# SSD_PINOUT.net
KiCad netlist of a schematic drawn in Altium Designer
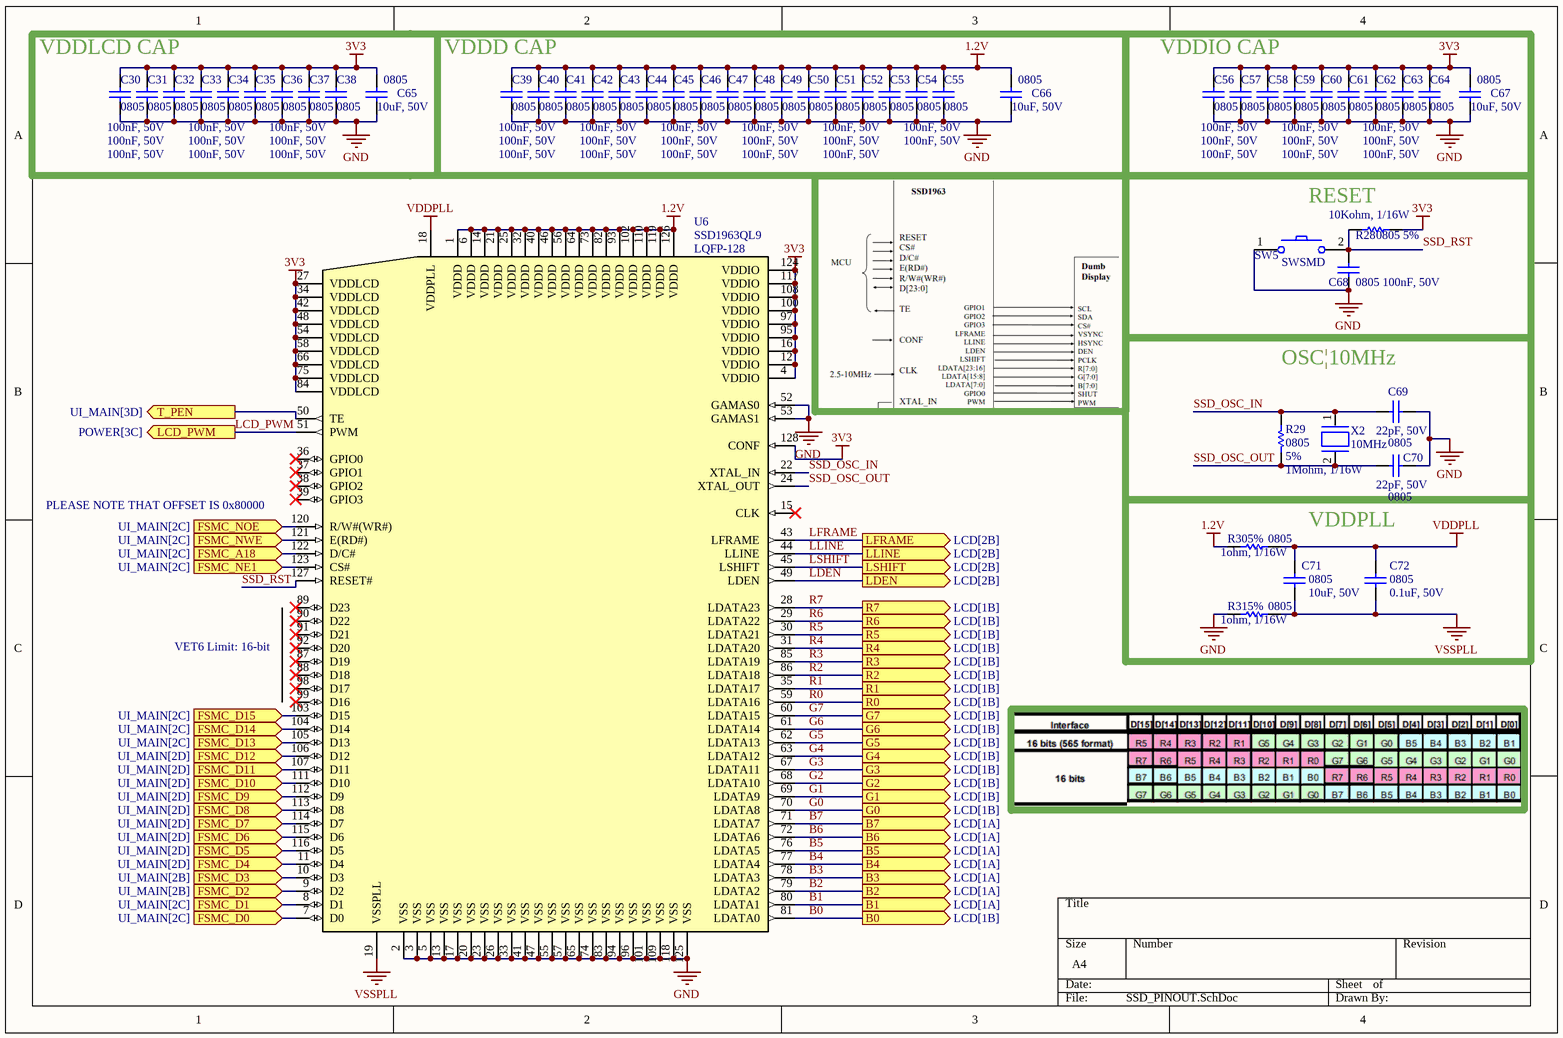
[diagram p0: SSD_PINOUT.SchDoc]

(export (version "E")
  (design (tool "Eeschema 10.0.6"))
  (components
    (comp (ref "C30")
      (value "100nF, 50V")
      (footprint "C_0805")
      (description "CAP_0805")
      (fields (field (name "PACKAGE") "0805"))
      (libsource (lib "DisplayLib") (part "CAP_0805"))
    )
    (comp (ref "C31")
      (value "100nF, 50V")
      (footprint "C_0805")
      (description "CAP_0805")
      (fields (field (name "PACKAGE") "0805"))
      (libsource (lib "DisplayLib") (part "CAP_0805"))
    )
    (comp (ref "C32")
      (value "100nF, 50V")
      (footprint "C_0805")
      (description "CAP_0805")
      (fields (field (name "PACKAGE") "0805"))
      (libsource (lib "DisplayLib") (part "CAP_0805"))
    )
    (comp (ref "C33")
      (value "100nF, 50V")
      (footprint "C_0805")
      (description "CAP_0805")
      (fields (field (name "PACKAGE") "0805"))
      (libsource (lib "DisplayLib") (part "CAP_0805"))
    )
    (comp (ref "C34")
      (value "100nF, 50V")
      (footprint "C_0805")
      (description "CAP_0805")
      (fields (field (name "PACKAGE") "0805"))
      (libsource (lib "DisplayLib") (part "CAP_0805"))
    )
    (comp (ref "C35")
      (value "100nF, 50V")
      (footprint "C_0805")
      (description "CAP_0805")
      (fields (field (name "PACKAGE") "0805"))
      (libsource (lib "DisplayLib") (part "CAP_0805"))
    )
    (comp (ref "C36")
      (value "100nF, 50V")
      (footprint "C_0805")
      (description "CAP_0805")
      (fields (field (name "PACKAGE") "0805"))
      (libsource (lib "DisplayLib") (part "CAP_0805"))
    )
    (comp (ref "C37")
      (value "100nF, 50V")
      (footprint "C_0805")
      (description "CAP_0805")
      (fields (field (name "PACKAGE") "0805"))
      (libsource (lib "DisplayLib") (part "CAP_0805"))
    )
    (comp (ref "C38")
      (value "100nF, 50V")
      (footprint "C_0805")
      (description "CAP_0805")
      (fields (field (name "PACKAGE") "0805"))
      (libsource (lib "DisplayLib") (part "CAP_0805"))
    )
    (comp (ref "C39")
      (value "100nF, 50V")
      (footprint "C_0805")
      (description "CAP_0805")
      (fields (field (name "PACKAGE") "0805"))
      (libsource (lib "DisplayLib") (part "CAP_0805"))
    )
    (comp (ref "C40")
      (value "100nF, 50V")
      (footprint "C_0805")
      (description "CAP_0805")
      (fields (field (name "PACKAGE") "0805"))
      (libsource (lib "DisplayLib") (part "CAP_0805"))
    )
    (comp (ref "C41")
      (value "100nF, 50V")
      (footprint "C_0805")
      (description "CAP_0805")
      (fields (field (name "PACKAGE") "0805"))
      (libsource (lib "DisplayLib") (part "CAP_0805"))
    )
    (comp (ref "C42")
      (value "100nF, 50V")
      (footprint "C_0805")
      (description "CAP_0805")
      (fields (field (name "PACKAGE") "0805"))
      (libsource (lib "DisplayLib") (part "CAP_0805"))
    )
    (comp (ref "C43")
      (value "100nF, 50V")
      (footprint "C_0805")
      (description "CAP_0805")
      (fields (field (name "PACKAGE") "0805"))
      (libsource (lib "DisplayLib") (part "CAP_0805"))
    )
    (comp (ref "C44")
      (value "100nF, 50V")
      (footprint "C_0805")
      (description "CAP_0805")
      (fields (field (name "PACKAGE") "0805"))
      (libsource (lib "DisplayLib") (part "CAP_0805"))
    )
    (comp (ref "C45")
      (value "100nF, 50V")
      (footprint "C_0805")
      (description "CAP_0805")
      (fields (field (name "PACKAGE") "0805"))
      (libsource (lib "DisplayLib") (part "CAP_0805"))
    )
    (comp (ref "C46")
      (value "100nF, 50V")
      (footprint "C_0805")
      (description "CAP_0805")
      (fields (field (name "PACKAGE") "0805"))
      (libsource (lib "DisplayLib") (part "CAP_0805"))
    )
    (comp (ref "C47")
      (value "100nF, 50V")
      (footprint "C_0805")
      (description "CAP_0805")
      (fields (field (name "PACKAGE") "0805"))
      (libsource (lib "DisplayLib") (part "CAP_0805"))
    )
    (comp (ref "C48")
      (value "100nF, 50V")
      (footprint "C_0805")
      (description "CAP_0805")
      (fields (field (name "PACKAGE") "0805"))
      (libsource (lib "DisplayLib") (part "CAP_0805"))
    )
    (comp (ref "C49")
      (value "100nF, 50V")
      (footprint "C_0805")
      (description "CAP_0805")
      (fields (field (name "PACKAGE") "0805"))
      (libsource (lib "DisplayLib") (part "CAP_0805"))
    )
    (comp (ref "C50")
      (value "100nF, 50V")
      (footprint "C_0805")
      (description "CAP_0805")
      (fields (field (name "PACKAGE") "0805"))
      (libsource (lib "DisplayLib") (part "CAP_0805"))
    )
    (comp (ref "C51")
      (value "100nF, 50V")
      (footprint "C_0805")
      (description "CAP_0805")
      (fields (field (name "PACKAGE") "0805"))
      (libsource (lib "DisplayLib") (part "CAP_0805"))
    )
    (comp (ref "C52")
      (value "100nF, 50V")
      (footprint "C_0805")
      (description "CAP_0805")
      (fields (field (name "PACKAGE") "0805"))
      (libsource (lib "DisplayLib") (part "CAP_0805"))
    )
    (comp (ref "C53")
      (value "100nF, 50V")
      (footprint "C_0805")
      (description "CAP_0805")
      (fields (field (name "PACKAGE") "0805"))
      (libsource (lib "DisplayLib") (part "CAP_0805"))
    )
    (comp (ref "C54")
      (value "100nF, 50V")
      (footprint "C_0805")
      (description "CAP_0805")
      (fields (field (name "PACKAGE") "0805"))
      (libsource (lib "DisplayLib") (part "CAP_0805"))
    )
    (comp (ref "C55")
      (value "100nF, 50V")
      (footprint "C_0805")
      (description "CAP_0805")
      (fields (field (name "PACKAGE") "0805"))
      (libsource (lib "DisplayLib") (part "CAP_0805"))
    )
    (comp (ref "C56")
      (value "100nF, 50V")
      (footprint "C_0805")
      (description "CAP_0805")
      (fields (field (name "PACKAGE") "0805"))
      (libsource (lib "DisplayLib") (part "CAP_0805"))
    )
    (comp (ref "C57")
      (value "100nF, 50V")
      (footprint "C_0805")
      (description "CAP_0805")
      (fields (field (name "PACKAGE") "0805"))
      (libsource (lib "DisplayLib") (part "CAP_0805"))
    )
    (comp (ref "C58")
      (value "100nF, 50V")
      (footprint "C_0805")
      (description "CAP_0805")
      (fields (field (name "PACKAGE") "0805"))
      (libsource (lib "DisplayLib") (part "CAP_0805"))
    )
    (comp (ref "C59")
      (value "100nF, 50V")
      (footprint "C_0805")
      (description "CAP_0805")
      (fields (field (name "PACKAGE") "0805"))
      (libsource (lib "DisplayLib") (part "CAP_0805"))
    )
    (comp (ref "C60")
      (value "100nF, 50V")
      (footprint "C_0805")
      (description "CAP_0805")
      (fields (field (name "PACKAGE") "0805"))
      (libsource (lib "DisplayLib") (part "CAP_0805"))
    )
    (comp (ref "C61")
      (value "100nF, 50V")
      (footprint "C_0805")
      (description "CAP_0805")
      (fields (field (name "PACKAGE") "0805"))
      (libsource (lib "DisplayLib") (part "CAP_0805"))
    )
    (comp (ref "C62")
      (value "100nF, 50V")
      (footprint "C_0805")
      (description "CAP_0805")
      (fields (field (name "PACKAGE") "0805"))
      (libsource (lib "DisplayLib") (part "CAP_0805"))
    )
    (comp (ref "C63")
      (value "100nF, 50V")
      (footprint "C_0805")
      (description "CAP_0805")
      (fields (field (name "PACKAGE") "0805"))
      (libsource (lib "DisplayLib") (part "CAP_0805"))
    )
    (comp (ref "C64")
      (value "100nF, 50V")
      (footprint "C_0805")
      (description "CAP_0805")
      (fields (field (name "PACKAGE") "0805"))
      (libsource (lib "DisplayLib") (part "CAP_0805"))
    )
    (comp (ref "C65")
      (value "10uF, 50V")
      (footprint "C_0805")
      (description "CAP_0805")
      (fields (field (name "PACKAGE") "0805"))
      (libsource (lib "DisplayLib") (part "CAP_0805"))
    )
    (comp (ref "C66")
      (value "10uF, 50V")
      (footprint "C_0805")
      (description "CAP_0805")
      (fields (field (name "PACKAGE") "0805"))
      (libsource (lib "DisplayLib") (part "CAP_0805"))
    )
    (comp (ref "C67")
      (value "10uF, 50V")
      (footprint "C_0805")
      (description "CAP_0805")
      (fields (field (name "PACKAGE") "0805"))
      (libsource (lib "DisplayLib") (part "CAP_0805"))
    )
    (comp (ref "C68")
      (value "100nF, 50V")
      (footprint "C_0805")
      (description "CAP_0805")
      (fields (field (name "PACKAGE") "0805"))
      (libsource (lib "DisplayLib") (part "CAP_0805"))
    )
    (comp (ref "C69")
      (value "22pF, 50V")
      (footprint "C_0805")
      (description "CAP_0805")
      (fields (field (name "PACKAGE") "0805"))
      (libsource (lib "DisplayLib") (part "CAP_0805"))
    )
    (comp (ref "C70")
      (value "22pF, 50V")
      (footprint "C_0805")
      (description "CAP_0805")
      (fields (field (name "PACKAGE") "0805"))
      (libsource (lib "DisplayLib") (part "CAP_0805"))
    )
    (comp (ref "C71")
      (value "10uF, 50V")
      (footprint "C_0805")
      (description "CAP_0805")
      (fields (field (name "PACKAGE") "0805"))
      (libsource (lib "DisplayLib") (part "CAP_0805"))
    )
    (comp (ref "C72")
      (value "0.1uF, 50V")
      (footprint "C_0805")
      (description "CAP_0805")
      (fields (field (name "PACKAGE") "0805"))
      (libsource (lib "DisplayLib") (part "CAP_0805"))
    )
    (comp (ref "R28")
      (value "10Kohm, 1/16W")
      (footprint "R_0805")
      (description "RES_0805")
      (fields (field (name "PACKAGE") "0805") (field (name "ACC") "5%"))
      (libsource (lib "DisplayLib") (part "RES_0805"))
    )
    (comp (ref "R29")
      (value "1Mohm, 1/16W")
      (footprint "R_0805")
      (description "RES_0805")
      (fields (field (name "PACKAGE") "0805") (field (name "ACC") "5%"))
      (libsource (lib "DisplayLib") (part "RES_0805"))
    )
    (comp (ref "R30")
      (value "1ohm, 1/16W")
      (footprint "R_0805")
      (description "RES_0805")
      (fields (field (name "PACKAGE") "0805") (field (name "ACC") "5%"))
      (libsource (lib "DisplayLib") (part "RES_0805"))
    )
    (comp (ref "R31")
      (value "1ohm, 1/16W")
      (footprint "R_0805")
      (description "RES_0805")
      (fields (field (name "PACKAGE") "0805") (field (name "ACC") "5%"))
      (libsource (lib "DisplayLib") (part "RES_0805"))
    )
    (comp (ref "SW5")
      (value "SWSMD")
      (footprint "SW_SMD_NOGND")
      (description "SW_SMD")
      (libsource (lib "DisplayLib") (part "SWSMD_NOGND"))
    )
    (comp (ref "U6")
      (value "SSD1963QL9")
      (footprint "PKG_LQFP-128")
      (description "1215KB Embedded Display SRAM\r\nLCD Display Controller")
      (fields (field (name "PACKAGE") "LQFP-128"))
      (libsource (lib "DisplayLib") (part "SSD1963QL9"))
    )
    (comp (ref "X2")
      (value "10MHz")
      (footprint "PKG_HC49-S")
      (description "Crystal, 10 MHz, -30 to 85 degC, 3.2 x 2.5 x 0.9 mm SMD")
      (libsource (lib "DisplayLib") (part "XTAL_8MHZ"))
    )
  )
  (nets
    (net (code "1") (name "/B0") (class "Default")
      (node (ref "U6") (pin "81") (pinfunction "LDATA0_81") (pintype "output"))
    )
    (net (code "2") (name "/B1") (class "Default")
      (node (ref "U6") (pin "80") (pinfunction "LDATA1_80") (pintype "output"))
    )
    (net (code "3") (name "/B2") (class "Default")
      (node (ref "U6") (pin "79") (pinfunction "LDATA2_79") (pintype "output"))
    )
    (net (code "4") (name "/B3") (class "Default")
      (node (ref "U6") (pin "78") (pinfunction "LDATA3_78") (pintype "output"))
    )
    (net (code "5") (name "/B4") (class "Default")
      (node (ref "U6") (pin "77") (pinfunction "LDATA4_77") (pintype "output"))
    )
    (net (code "6") (name "/B5") (class "Default")
      (node (ref "U6") (pin "76") (pinfunction "LDATA5_76") (pintype "output"))
    )
    (net (code "7") (name "/B6") (class "Default")
      (node (ref "U6") (pin "72") (pinfunction "LDATA6_72") (pintype "output"))
    )
    (net (code "8") (name "/B7") (class "Default")
      (node (ref "U6") (pin "71") (pinfunction "LDATA7_71") (pintype "output"))
    )
    (net (code "9") (name "/FSMC_A18") (class "Default")
      (node (ref "U6") (pin "122") (pinfunction "D/C#_122") (pintype "input"))
    )
    (net (code "10") (name "/FSMC_D0") (class "Default")
      (node (ref "U6") (pin "7") (pinfunction "D0_7") (pintype "bidirectional"))
    )
    (net (code "11") (name "/FSMC_D1") (class "Default")
      (node (ref "U6") (pin "8") (pinfunction "D1_8") (pintype "bidirectional"))
    )
    (net (code "12") (name "/FSMC_D2") (class "Default")
      (node (ref "U6") (pin "9") (pinfunction "D2_9") (pintype "bidirectional"))
    )
    (net (code "13") (name "/FSMC_D3") (class "Default")
      (node (ref "U6") (pin "10") (pinfunction "D3_10") (pintype "bidirectional"))
    )
    (net (code "14") (name "/FSMC_D4") (class "Default")
      (node (ref "U6") (pin "11") (pinfunction "D4_11") (pintype "bidirectional"))
    )
    (net (code "15") (name "/FSMC_D5") (class "Default")
      (node (ref "U6") (pin "116") (pinfunction "D5_116") (pintype "bidirectional"))
    )
    (net (code "16") (name "/FSMC_D6") (class "Default")
      (node (ref "U6") (pin "115") (pinfunction "D6_115") (pintype "bidirectional"))
    )
    (net (code "17") (name "/FSMC_D7") (class "Default")
      (node (ref "U6") (pin "114") (pinfunction "D7_114") (pintype "bidirectional"))
    )
    (net (code "18") (name "/FSMC_D8") (class "Default")
      (node (ref "U6") (pin "113") (pinfunction "D8_113") (pintype "bidirectional"))
    )
    (net (code "19") (name "/FSMC_D9") (class "Default")
      (node (ref "U6") (pin "112") (pinfunction "D9_112") (pintype "bidirectional"))
    )
    (net (code "20") (name "/FSMC_D10") (class "Default")
      (node (ref "U6") (pin "111") (pinfunction "D10_111") (pintype "bidirectional"))
    )
    (net (code "21") (name "/FSMC_D11") (class "Default")
      (node (ref "U6") (pin "107") (pinfunction "D11_107") (pintype "bidirectional"))
    )
    (net (code "22") (name "/FSMC_D12") (class "Default")
      (node (ref "U6") (pin "106") (pinfunction "D12_106") (pintype "bidirectional"))
    )
    (net (code "23") (name "/FSMC_D13") (class "Default")
      (node (ref "U6") (pin "105") (pinfunction "D13_105") (pintype "bidirectional"))
    )
    (net (code "24") (name "/FSMC_D14") (class "Default")
      (node (ref "U6") (pin "104") (pinfunction "D14_104") (pintype "bidirectional"))
    )
    (net (code "25") (name "/FSMC_D15") (class "Default")
      (node (ref "U6") (pin "103") (pinfunction "D15_103") (pintype "bidirectional"))
    )
    (net (code "26") (name "/FSMC_NE1") (class "Default")
      (node (ref "U6") (pin "123") (pinfunction "CS#_123") (pintype "input"))
    )
    (net (code "27") (name "/FSMC_NOE") (class "Default")
      (node (ref "U6") (pin "120") (pinfunction "R/W#(WR#)_120") (pintype "input"))
    )
    (net (code "28") (name "/FSMC_NWE") (class "Default")
      (node (ref "U6") (pin "121") (pinfunction "E(RD#)_121") (pintype "input"))
    )
    (net (code "29") (name "/G0") (class "Default")
      (node (ref "U6") (pin "70") (pinfunction "LDATA8_70") (pintype "output"))
    )
    (net (code "30") (name "/G1") (class "Default")
      (node (ref "U6") (pin "69") (pinfunction "LDATA9_69") (pintype "output"))
    )
    (net (code "31") (name "/G2") (class "Default")
      (node (ref "U6") (pin "68") (pinfunction "LDATA10_68") (pintype "output"))
    )
    (net (code "32") (name "/G3") (class "Default")
      (node (ref "U6") (pin "67") (pinfunction "LDATA11_67") (pintype "output"))
    )
    (net (code "33") (name "/G4") (class "Default")
      (node (ref "U6") (pin "63") (pinfunction "LDATA12_63") (pintype "output"))
    )
    (net (code "34") (name "/G5") (class "Default")
      (node (ref "U6") (pin "62") (pinfunction "LDATA13_62") (pintype "output"))
    )
    (net (code "35") (name "/G6") (class "Default")
      (node (ref "U6") (pin "61") (pinfunction "LDATA14_61") (pintype "output"))
    )
    (net (code "36") (name "/G7") (class "Default")
      (node (ref "U6") (pin "60") (pinfunction "LDATA15_60") (pintype "output"))
    )
    (net (code "37") (name "/LCD_PWM") (class "Default")
      (node (ref "U6") (pin "51") (pinfunction "PWM_51") (pintype "output"))
    )
    (net (code "38") (name "/LDEN") (class "Default")
      (node (ref "U6") (pin "49") (pinfunction "LDEN_49") (pintype "output"))
    )
    (net (code "39") (name "/LFRAME") (class "Default")
      (node (ref "U6") (pin "43") (pinfunction "LFRAME_43") (pintype "output"))
    )
    (net (code "40") (name "/LLINE") (class "Default")
      (node (ref "U6") (pin "44") (pinfunction "LLINE_44") (pintype "output"))
    )
    (net (code "41") (name "/LSHIFT") (class "Default")
      (node (ref "U6") (pin "45") (pinfunction "LSHIFT_45") (pintype "output"))
    )
    (net (code "42") (name "/R0") (class "Default")
      (node (ref "U6") (pin "59") (pinfunction "LDATA16_59") (pintype "output"))
    )
    (net (code "43") (name "/R1") (class "Default")
      (node (ref "U6") (pin "35") (pinfunction "LDATA17_35") (pintype "output"))
    )
    (net (code "44") (name "/R2") (class "Default")
      (node (ref "U6") (pin "86") (pinfunction "LDATA18_86") (pintype "output"))
    )
    (net (code "45") (name "/R3") (class "Default")
      (node (ref "U6") (pin "85") (pinfunction "LDATA19_85") (pintype "output"))
    )
    (net (code "46") (name "/R4") (class "Default")
      (node (ref "U6") (pin "31") (pinfunction "LDATA20_31") (pintype "output"))
    )
    (net (code "47") (name "/R5") (class "Default")
      (node (ref "U6") (pin "30") (pinfunction "LDATA21_30") (pintype "output"))
    )
    (net (code "48") (name "/R6") (class "Default")
      (node (ref "U6") (pin "29") (pinfunction "LDATA22_29") (pintype "output"))
    )
    (net (code "49") (name "/R7") (class "Default")
      (node (ref "U6") (pin "28") (pinfunction "LDATA23_28") (pintype "output"))
    )
    (net (code "50") (name "/SSD_OSC_IN") (class "Default")
      (node (ref "C69") (pin "2") (pinfunction "2_2") (pintype "passive"))
      (node (ref "R29") (pin "1") (pinfunction "1_1") (pintype "passive"))
      (node (ref "U6") (pin "22") (pinfunction "XTAL_IN_22") (pintype "input"))
      (node (ref "X2") (pin "1") (pinfunction "1_1") (pintype "passive"))
    )
    (net (code "51") (name "/SSD_OSC_OUT") (class "Default")
      (node (ref "C70") (pin "2") (pinfunction "2_2") (pintype "passive"))
      (node (ref "R29") (pin "2") (pinfunction "2_2") (pintype "passive"))
      (node (ref "U6") (pin "24") (pinfunction "XTAL_OUT_24") (pintype "output"))
      (node (ref "X2") (pin "2") (pinfunction "2_2") (pintype "passive"))
    )
    (net (code "52") (name "/SSD_RST") (class "Default")
      (node (ref "C68") (pin "2") (pinfunction "2_2") (pintype "passive"))
      (node (ref "R28") (pin "2") (pinfunction "2_2") (pintype "passive"))
      (node (ref "SW5") (pin "2") (pinfunction "2_2") (pintype "passive"))
      (node (ref "U6") (pin "127") (pinfunction "RESET#_127") (pintype "input"))
    )
    (net (code "53") (name "/T_PEN") (class "Default")
      (node (ref "U6") (pin "50") (pinfunction "TE_50") (pintype "output"))
    )
    (net (code "54") (name "1.2V") (class "Default")
      (node (ref "C39") (pin "2") (pinfunction "2_2") (pintype "passive"))
      (node (ref "C40") (pin "2") (pinfunction "2_2") (pintype "passive"))
      (node (ref "C41") (pin "2") (pinfunction "2_2") (pintype "passive"))
      (node (ref "C42") (pin "2") (pinfunction "2_2") (pintype "passive"))
      (node (ref "C43") (pin "2") (pinfunction "2_2") (pintype "passive"))
      (node (ref "C44") (pin "2") (pinfunction "2_2") (pintype "passive"))
      (node (ref "C45") (pin "2") (pinfunction "2_2") (pintype "passive"))
      (node (ref "C46") (pin "2") (pinfunction "2_2") (pintype "passive"))
      (node (ref "C47") (pin "2") (pinfunction "2_2") (pintype "passive"))
      (node (ref "C48") (pin "2") (pinfunction "2_2") (pintype "passive"))
      (node (ref "C49") (pin "2") (pinfunction "2_2") (pintype "passive"))
      (node (ref "C50") (pin "2") (pinfunction "2_2") (pintype "passive"))
      (node (ref "C51") (pin "2") (pinfunction "2_2") (pintype "passive"))
      (node (ref "C52") (pin "2") (pinfunction "2_2") (pintype "passive"))
      (node (ref "C53") (pin "2") (pinfunction "2_2") (pintype "passive"))
      (node (ref "C54") (pin "2") (pinfunction "2_2") (pintype "passive"))
      (node (ref "C55") (pin "2") (pinfunction "2_2") (pintype "passive"))
      (node (ref "C66") (pin "2") (pinfunction "2_2") (pintype "passive"))
      (node (ref "R30") (pin "2") (pinfunction "2_2") (pintype "passive"))
      (node (ref "U6") (pin "1") (pinfunction "VDDD_1") (pintype "power_in"))
      (node (ref "U6") (pin "102") (pinfunction "VDDD_102") (pintype "power_in"))
      (node (ref "U6") (pin "110") (pinfunction "VDDD_110") (pintype "power_in"))
      (node (ref "U6") (pin "119") (pinfunction "VDDD_119") (pintype "power_in"))
      (node (ref "U6") (pin "126") (pinfunction "VDDD_126") (pintype "power_in"))
      (node (ref "U6") (pin "14") (pinfunction "VDDD_14") (pintype "power_in"))
      (node (ref "U6") (pin "21") (pinfunction "VDDD_21") (pintype "power_in"))
      (node (ref "U6") (pin "25") (pinfunction "VDDD_25") (pintype "power_in"))
      (node (ref "U6") (pin "32") (pinfunction "VDDD_32") (pintype "power_in"))
      (node (ref "U6") (pin "40") (pinfunction "VDDD_40") (pintype "power_in"))
      (node (ref "U6") (pin "46") (pinfunction "VDDD_46") (pintype "power_in"))
      (node (ref "U6") (pin "56") (pinfunction "VDDD_56") (pintype "power_in"))
      (node (ref "U6") (pin "6") (pinfunction "VDDD_6") (pintype "power_in"))
      (node (ref "U6") (pin "64") (pinfunction "VDDD_64") (pintype "power_in"))
      (node (ref "U6") (pin "73") (pinfunction "VDDD_73") (pintype "power_in"))
      (node (ref "U6") (pin "82") (pinfunction "VDDD_82") (pintype "power_in"))
      (node (ref "U6") (pin "93") (pinfunction "VDDD_93") (pintype "power_in"))
    )
    (net (code "55") (name "3V3") (class "Default")
      (node (ref "C30") (pin "2") (pinfunction "2_2") (pintype "passive"))
      (node (ref "C31") (pin "2") (pinfunction "2_2") (pintype "passive"))
      (node (ref "C32") (pin "2") (pinfunction "2_2") (pintype "passive"))
      (node (ref "C33") (pin "2") (pinfunction "2_2") (pintype "passive"))
      (node (ref "C34") (pin "2") (pinfunction "2_2") (pintype "passive"))
      (node (ref "C35") (pin "2") (pinfunction "2_2") (pintype "passive"))
      (node (ref "C36") (pin "2") (pinfunction "2_2") (pintype "passive"))
      (node (ref "C37") (pin "2") (pinfunction "2_2") (pintype "passive"))
      (node (ref "C38") (pin "2") (pinfunction "2_2") (pintype "passive"))
      (node (ref "C56") (pin "2") (pinfunction "2_2") (pintype "passive"))
      (node (ref "C57") (pin "2") (pinfunction "2_2") (pintype "passive"))
      (node (ref "C58") (pin "2") (pinfunction "2_2") (pintype "passive"))
      (node (ref "C59") (pin "2") (pinfunction "2_2") (pintype "passive"))
      (node (ref "C60") (pin "2") (pinfunction "2_2") (pintype "passive"))
      (node (ref "C61") (pin "2") (pinfunction "2_2") (pintype "passive"))
      (node (ref "C62") (pin "2") (pinfunction "2_2") (pintype "passive"))
      (node (ref "C63") (pin "2") (pinfunction "2_2") (pintype "passive"))
      (node (ref "C64") (pin "2") (pinfunction "2_2") (pintype "passive"))
      (node (ref "C65") (pin "2") (pinfunction "2_2") (pintype "passive"))
      (node (ref "C67") (pin "2") (pinfunction "2_2") (pintype "passive"))
      (node (ref "R28") (pin "1") (pinfunction "1_1") (pintype "passive"))
      (node (ref "U6") (pin "100") (pinfunction "VDDIO_100") (pintype "power_in"))
      (node (ref "U6") (pin "108") (pinfunction "VDDIO_108") (pintype "power_in"))
      (node (ref "U6") (pin "117") (pinfunction "VDDIO_117") (pintype "power_in"))
      (node (ref "U6") (pin "12") (pinfunction "VDDIO_12") (pintype "power_in"))
      (node (ref "U6") (pin "124") (pinfunction "VDDIO_124") (pintype "power_in"))
      (node (ref "U6") (pin "128") (pinfunction "CONF_128") (pintype "input"))
      (node (ref "U6") (pin "16") (pinfunction "VDDIO_16") (pintype "power_in"))
      (node (ref "U6") (pin "27") (pinfunction "VDDLCD_27") (pintype "power_in"))
      (node (ref "U6") (pin "34") (pinfunction "VDDLCD_34") (pintype "power_in"))
      (node (ref "U6") (pin "4") (pinfunction "VDDIO_4") (pintype "power_in"))
      (node (ref "U6") (pin "42") (pinfunction "VDDLCD_42") (pintype "power_in"))
      (node (ref "U6") (pin "48") (pinfunction "VDDLCD_48") (pintype "power_in"))
      (node (ref "U6") (pin "54") (pinfunction "VDDLCD_54") (pintype "power_in"))
      (node (ref "U6") (pin "58") (pinfunction "VDDLCD_58") (pintype "power_in"))
      (node (ref "U6") (pin "66") (pinfunction "VDDLCD_66") (pintype "power_in"))
      (node (ref "U6") (pin "75") (pinfunction "VDDLCD_75") (pintype "power_in"))
      (node (ref "U6") (pin "84") (pinfunction "VDDLCD_84") (pintype "power_in"))
      (node (ref "U6") (pin "95") (pinfunction "VDDIO_95") (pintype "power_in"))
      (node (ref "U6") (pin "97") (pinfunction "VDDIO_97") (pintype "power_in"))
    )
    (net (code "56") (name "GND") (class "Default")
      (node (ref "C30") (pin "1") (pinfunction "1_1") (pintype "passive"))
      (node (ref "C31") (pin "1") (pinfunction "1_1") (pintype "passive"))
      (node (ref "C32") (pin "1") (pinfunction "1_1") (pintype "passive"))
      (node (ref "C33") (pin "1") (pinfunction "1_1") (pintype "passive"))
      (node (ref "C34") (pin "1") (pinfunction "1_1") (pintype "passive"))
      (node (ref "C35") (pin "1") (pinfunction "1_1") (pintype "passive"))
      (node (ref "C36") (pin "1") (pinfunction "1_1") (pintype "passive"))
      (node (ref "C37") (pin "1") (pinfunction "1_1") (pintype "passive"))
      (node (ref "C38") (pin "1") (pinfunction "1_1") (pintype "passive"))
      (node (ref "C39") (pin "1") (pinfunction "1_1") (pintype "passive"))
      (node (ref "C40") (pin "1") (pinfunction "1_1") (pintype "passive"))
      (node (ref "C41") (pin "1") (pinfunction "1_1") (pintype "passive"))
      (node (ref "C42") (pin "1") (pinfunction "1_1") (pintype "passive"))
      (node (ref "C43") (pin "1") (pinfunction "1_1") (pintype "passive"))
      (node (ref "C44") (pin "1") (pinfunction "1_1") (pintype "passive"))
      (node (ref "C45") (pin "1") (pinfunction "1_1") (pintype "passive"))
      (node (ref "C46") (pin "1") (pinfunction "1_1") (pintype "passive"))
      (node (ref "C47") (pin "1") (pinfunction "1_1") (pintype "passive"))
      (node (ref "C48") (pin "1") (pinfunction "1_1") (pintype "passive"))
      (node (ref "C49") (pin "1") (pinfunction "1_1") (pintype "passive"))
      (node (ref "C50") (pin "1") (pinfunction "1_1") (pintype "passive"))
      (node (ref "C51") (pin "1") (pinfunction "1_1") (pintype "passive"))
      (node (ref "C52") (pin "1") (pinfunction "1_1") (pintype "passive"))
      (node (ref "C53") (pin "1") (pinfunction "1_1") (pintype "passive"))
      (node (ref "C54") (pin "1") (pinfunction "1_1") (pintype "passive"))
      (node (ref "C55") (pin "1") (pinfunction "1_1") (pintype "passive"))
      (node (ref "C56") (pin "1") (pinfunction "1_1") (pintype "passive"))
      (node (ref "C57") (pin "1") (pinfunction "1_1") (pintype "passive"))
      (node (ref "C58") (pin "1") (pinfunction "1_1") (pintype "passive"))
      (node (ref "C59") (pin "1") (pinfunction "1_1") (pintype "passive"))
      (node (ref "C60") (pin "1") (pinfunction "1_1") (pintype "passive"))
      (node (ref "C61") (pin "1") (pinfunction "1_1") (pintype "passive"))
      (node (ref "C62") (pin "1") (pinfunction "1_1") (pintype "passive"))
      (node (ref "C63") (pin "1") (pinfunction "1_1") (pintype "passive"))
      (node (ref "C64") (pin "1") (pinfunction "1_1") (pintype "passive"))
      (node (ref "C65") (pin "1") (pinfunction "1_1") (pintype "passive"))
      (node (ref "C66") (pin "1") (pinfunction "1_1") (pintype "passive"))
      (node (ref "C67") (pin "1") (pinfunction "1_1") (pintype "passive"))
      (node (ref "C68") (pin "1") (pinfunction "1_1") (pintype "passive"))
      (node (ref "C69") (pin "1") (pinfunction "1_1") (pintype "passive"))
      (node (ref "C70") (pin "1") (pinfunction "1_1") (pintype "passive"))
      (node (ref "R31") (pin "2") (pinfunction "2_2") (pintype "passive"))
      (node (ref "SW5") (pin "1") (pinfunction "1_1") (pintype "passive"))
      (node (ref "U6") (pin "101") (pinfunction "VSS_101") (pintype "power_in"))
      (node (ref "U6") (pin "109") (pinfunction "VSS_109") (pintype "power_in"))
      (node (ref "U6") (pin "118") (pinfunction "VSS_118") (pintype "power_in"))
      (node (ref "U6") (pin "125") (pinfunction "VSS_125") (pintype "power_in"))
      (node (ref "U6") (pin "13") (pinfunction "VSS_13") (pintype "power_in"))
      (node (ref "U6") (pin "17") (pinfunction "VSS_17") (pintype "power_in"))
      (node (ref "U6") (pin "2") (pinfunction "VSS_2") (pintype "power_in"))
      (node (ref "U6") (pin "20") (pinfunction "VSS_20") (pintype "power_in"))
      (node (ref "U6") (pin "23") (pinfunction "VSS_23") (pintype "power_in"))
      (node (ref "U6") (pin "26") (pinfunction "VSS_26") (pintype "power_in"))
      (node (ref "U6") (pin "3") (pinfunction "VSS_3") (pintype "power_in"))
      (node (ref "U6") (pin "33") (pinfunction "VSS_33") (pintype "power_in"))
      (node (ref "U6") (pin "41") (pinfunction "VSS_41") (pintype "power_in"))
      (node (ref "U6") (pin "47") (pinfunction "VSS_47") (pintype "power_in"))
      (node (ref "U6") (pin "5") (pinfunction "VSS_5") (pintype "power_in"))
      (node (ref "U6") (pin "52") (pinfunction "GAMAS0_52") (pintype "input"))
      (node (ref "U6") (pin "53") (pinfunction "GAMAS1_53") (pintype "input"))
      (node (ref "U6") (pin "55") (pinfunction "VSS_55") (pintype "power_in"))
      (node (ref "U6") (pin "57") (pinfunction "VSS_57") (pintype "power_in"))
      (node (ref "U6") (pin "65") (pinfunction "VSS_65") (pintype "power_in"))
      (node (ref "U6") (pin "74") (pinfunction "VSS_74") (pintype "power_in"))
      (node (ref "U6") (pin "83") (pinfunction "VSS_83") (pintype "power_in"))
      (node (ref "U6") (pin "94") (pinfunction "VSS_94") (pintype "power_in"))
      (node (ref "U6") (pin "96") (pinfunction "VSS_96") (pintype "power_in"))
    )
    (net (code "57") (name "VDDPLL") (class "Default")
      (node (ref "C71") (pin "2") (pinfunction "2_2") (pintype "passive"))
      (node (ref "C72") (pin "2") (pinfunction "2_2") (pintype "passive"))
      (node (ref "R30") (pin "1") (pinfunction "1_1") (pintype "passive"))
      (node (ref "U6") (pin "18") (pinfunction "VDDPLL_18") (pintype "power_in"))
    )
    (net (code "58") (name "VSSPLL") (class "Default")
      (node (ref "C71") (pin "1") (pinfunction "1_1") (pintype "passive"))
      (node (ref "C72") (pin "1") (pinfunction "1_1") (pintype "passive"))
      (node (ref "R31") (pin "1") (pinfunction "1_1") (pintype "passive"))
      (node (ref "U6") (pin "19") (pinfunction "VSSPLL_19") (pintype "power_in"))
    )
    (net (code "59") (name "unconnected-(U6-CLK-Pad15)") (class "Default")
      (node (ref "U6") (pin "15") (pinfunction "CLK_15") (pintype "input+no_connect"))
    )
    (net (code "60") (name "unconnected-(U6-D16-Pad99)") (class "Default")
      (node (ref "U6") (pin "99") (pinfunction "D16_99") (pintype "bidirectional+no_connect"))
    )
    (net (code "61") (name "unconnected-(U6-D17-Pad98)") (class "Default")
      (node (ref "U6") (pin "98") (pinfunction "D17_98") (pintype "bidirectional+no_connect"))
    )
    (net (code "62") (name "unconnected-(U6-D18-Pad88)") (class "Default")
      (node (ref "U6") (pin "88") (pinfunction "D18_88") (pintype "bidirectional+no_connect"))
    )
    (net (code "63") (name "unconnected-(U6-D19-Pad87)") (class "Default")
      (node (ref "U6") (pin "87") (pinfunction "D19_87") (pintype "bidirectional+no_connect"))
    )
    (net (code "64") (name "unconnected-(U6-D20-Pad92)") (class "Default")
      (node (ref "U6") (pin "92") (pinfunction "D20_92") (pintype "bidirectional+no_connect"))
    )
    (net (code "65") (name "unconnected-(U6-D21-Pad91)") (class "Default")
      (node (ref "U6") (pin "91") (pinfunction "D21_91") (pintype "bidirectional+no_connect"))
    )
    (net (code "66") (name "unconnected-(U6-D22-Pad90)") (class "Default")
      (node (ref "U6") (pin "90") (pinfunction "D22_90") (pintype "bidirectional+no_connect"))
    )
    (net (code "67") (name "unconnected-(U6-D23-Pad89)") (class "Default")
      (node (ref "U6") (pin "89") (pinfunction "D23_89") (pintype "bidirectional+no_connect"))
    )
    (net (code "68") (name "unconnected-(U6-GPIO0-Pad36)") (class "Default")
      (node (ref "U6") (pin "36") (pinfunction "GPIO0_36") (pintype "bidirectional+no_connect"))
    )
    (net (code "69") (name "unconnected-(U6-GPIO1-Pad37)") (class "Default")
      (node (ref "U6") (pin "37") (pinfunction "GPIO1_37") (pintype "bidirectional+no_connect"))
    )
    (net (code "70") (name "unconnected-(U6-GPIO2-Pad38)") (class "Default")
      (node (ref "U6") (pin "38") (pinfunction "GPIO2_38") (pintype "bidirectional+no_connect"))
    )
    (net (code "71") (name "unconnected-(U6-GPIO3-Pad39)") (class "Default")
      (node (ref "U6") (pin "39") (pinfunction "GPIO3_39") (pintype "bidirectional+no_connect"))
    )
  )
)
